# power_supply.net
KiCad netlist of a schematic drawn in Altium Designer
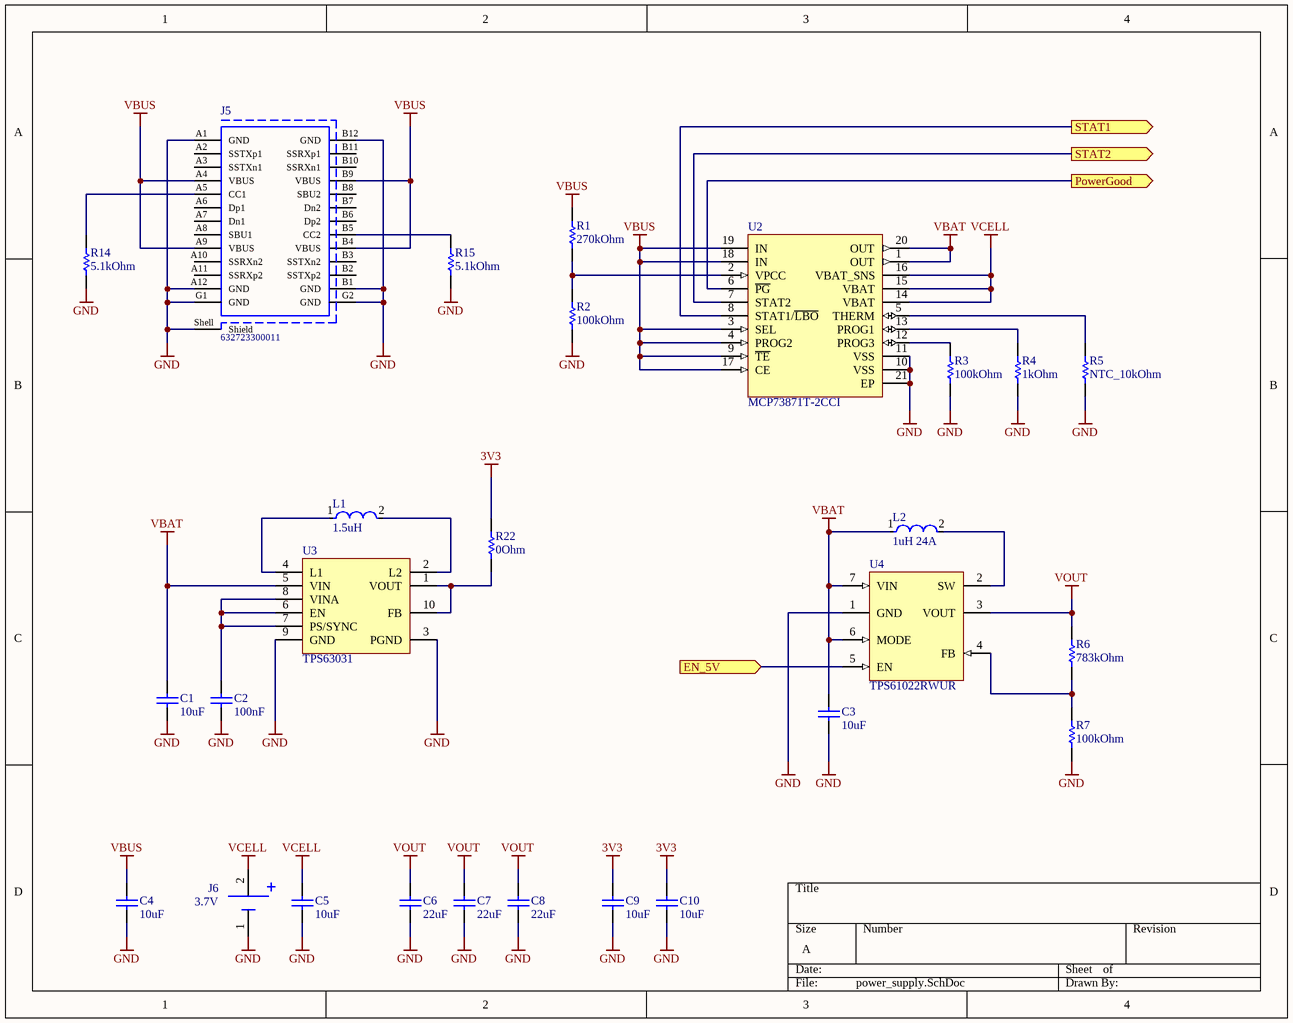
[diagram p0: power_supply.SchDoc]

(export (version "E")
  (design (tool "Eeschema 10.0.6"))
  (components
    (comp (ref "C1")
      (value "10uF")
      (footprint "CAP_0804")
      (fields
        (field (name "TOLERANCE") "10%")
        (field (name "PARTNUMBER") "1206GC102KAT1A")
        (field (name "MANUFACTURER") "AVX")
      )
      (libsource (lib "Schlib") (part "CAP_10UF"))
    )
    (comp (ref "C2")
      (value "100nF")
      (footprint "CAP_0804")
      (fields
        (field (name "TOLERANCE") "10%")
        (field (name "PARTNUMBER") "1206GC102KAT1A")
        (field (name "MANUFACTURER") "AVX")
      )
      (libsource (lib "Schlib") (part "CAP_100NF"))
    )
    (comp (ref "C3")
      (value "10uF")
      (footprint "CAP_0804")
      (fields
        (field (name "TOLERANCE") "10%")
        (field (name "PARTNUMBER") "1206GC102KAT1A")
        (field (name "MANUFACTURER") "AVX")
      )
      (libsource (lib "Schlib") (part "CAP_10UF"))
    )
    (comp (ref "C4")
      (value "10uF")
      (footprint "CAP_0804")
      (fields
        (field (name "TOLERANCE") "10%")
        (field (name "PARTNUMBER") "1206GC102KAT1A")
        (field (name "MANUFACTURER") "AVX")
      )
      (libsource (lib "Schlib") (part "CAP_10UF"))
    )
    (comp (ref "C5")
      (value "10uF")
      (footprint "CAP_0804")
      (fields
        (field (name "TOLERANCE") "10%")
        (field (name "PARTNUMBER") "1206GC102KAT1A")
        (field (name "MANUFACTURER") "AVX")
      )
      (libsource (lib "Schlib") (part "CAP_10UF"))
    )
    (comp (ref "C6")
      (value "22uF")
      (footprint "CAP_0804")
      (fields
        (field (name "TOLERANCE") "10%")
        (field (name "PARTNUMBER") "1206GC102KAT1A")
        (field (name "MANUFACTURER") "AVX")
      )
      (libsource (lib "Schlib") (part "CAP_22UF"))
    )
    (comp (ref "C7")
      (value "22uF")
      (footprint "CAP_0804")
      (fields
        (field (name "TOLERANCE") "10%")
        (field (name "PARTNUMBER") "1206GC102KAT1A")
        (field (name "MANUFACTURER") "AVX")
      )
      (libsource (lib "Schlib") (part "CAP_22UF"))
    )
    (comp (ref "C8")
      (value "22uF")
      (footprint "CAP_0804")
      (fields
        (field (name "TOLERANCE") "10%")
        (field (name "PARTNUMBER") "1206GC102KAT1A")
        (field (name "MANUFACTURER") "AVX")
      )
      (libsource (lib "Schlib") (part "CAP_22UF"))
    )
    (comp (ref "C9")
      (value "10uF")
      (footprint "CAP_0804")
      (fields
        (field (name "TOLERANCE") "10%")
        (field (name "PARTNUMBER") "1206GC102KAT1A")
        (field (name "MANUFACTURER") "AVX")
      )
      (libsource (lib "Schlib") (part "CAP_10UF"))
    )
    (comp (ref "C10")
      (value "10uF")
      (footprint "CAP_0804")
      (fields
        (field (name "TOLERANCE") "10%")
        (field (name "PARTNUMBER") "1206GC102KAT1A")
        (field (name "MANUFACTURER") "AVX")
      )
      (libsource (lib "Schlib") (part "CAP_10UF"))
    )
    (comp (ref "J5")
      (value "632723300011")
      (footprint "USB_C_FEMALE")
      (description "USB 3.1 Type C Receptacle WR-COM, Horizontal, SMT / THT")
      (fields (field (name "MANUFACTURER") "Wurth Elektronik") (field (name "PUBLISHER") "WurthElektronik"))
      (libsource (lib "Schlib") (part "USB_C_FEMALE"))
    )
    (comp (ref "J6")
      (value "3.7V")
      (footprint "BATTERY - duplicate")
      (description "CONN HEADER VERT 2POS 1.25MM")
      (fields
        (field (name "MANUFACTURER PART NUMBER") "53047-0210")
        (field (name "OCTOPART") "https://octopart.com/53047-0210-molex-276772")
      )
      (libsource (lib "Schlib") (part "BATTERY"))
    )
    (comp (ref "L1")
      (value "1.5uH")
      (footprint "INDUCTOR_1.5UH")
      (description "FIXED IND 1.5UH 7A 4.3 MOHM SMD")
      (fields (field (name "MANUFACTURER") "bourns") (field (name "MANUFACTURER PART NUMBER") "SRU1048-1R5Y"))
      (libsource (lib "Schlib") (part "INDUCTOR_1.5UH"))
    )
    (comp (ref "L2")
      (value "1uH 24A")
      (footprint "INDUCTOR_1UH")
      (description "FIXED IND 1UH 24A 3.5 MOHM SMD")
      (fields
        (field (name "OCTOPART") "https://octopart.com/srp1238a-1r0m-bourns-47099079")
        (field (name "MANUFACTURER PART NUMBER") "SRP1238A-1R0M")
      )
      (libsource (lib "Schlib") (part "INDUCTOR_1UH"))
    )
    (comp (ref "R1")
      (value "270kOhm")
      (footprint "RES_0804")
      (fields (field (name "PART NUMBER") "CRCW120647K0FKEA") (field (name "MANUFACTURER") "Vishay Dale"))
      (libsource (lib "Schlib") (part "RES_270K"))
    )
    (comp (ref "R2")
      (value "100kOhm")
      (footprint "RES_0804")
      (fields (field (name "PART NUMBER") "CRCW120647K0FKEA") (field (name "MANUFACTURER") "Vishay Dale"))
      (libsource (lib "Schlib") (part "RES_100K"))
    )
    (comp (ref "R3")
      (value "100kOhm")
      (footprint "RES_0804")
      (fields (field (name "PART NUMBER") "CRCW120647K0FKEA") (field (name "MANUFACTURER") "Vishay Dale"))
      (libsource (lib "Schlib") (part "RES_100K"))
    )
    (comp (ref "R4")
      (value "1kOhm")
      (footprint "RES_0804")
      (fields (field (name "PART NUMBER") "CRCW120647K0FKEA") (field (name "MANUFACTURER") "Vishay Dale"))
      (libsource (lib "Schlib") (part "RES_1K"))
    )
    (comp (ref "R5")
      (value "NTC_10kOhm")
      (footprint "RES_0804")
      (fields (field (name "MANUFACTURER") "Vishay Dale") (field (name "PART NUMBER") "NTHS1206N02N1002JE"))
      (libsource (lib "Schlib") (part "NTC_10K"))
    )
    (comp (ref "R6")
      (value "783kOhm")
      (footprint "RES_0804")
      (fields (field (name "PART NUMBER") "CRCW120647K0FKEA") (field (name "MANUFACTURER") "Vishay Dale"))
      (libsource (lib "Schlib") (part "RES_783K"))
    )
    (comp (ref "R7")
      (value "100kOhm")
      (footprint "RES_0804")
      (fields (field (name "PART NUMBER") "CRCW120647K0FKEA") (field (name "MANUFACTURER") "Vishay Dale"))
      (libsource (lib "Schlib") (part "RES_100K"))
    )
    (comp (ref "R14")
      (value "5.1kOhm")
      (footprint "RES_0804")
      (fields (field (name "PART NUMBER") "CRCW120647K0FKEA") (field (name "MANUFACTURER") "Vishay Dale"))
      (libsource (lib "Schlib") (part "RES_5.1K"))
    )
    (comp (ref "R15")
      (value "5.1kOhm")
      (footprint "RES_0804")
      (fields (field (name "PART NUMBER") "CRCW120647K0FKEA") (field (name "MANUFACTURER") "Vishay Dale"))
      (libsource (lib "Schlib") (part "RES_5.1K"))
    )
    (comp (ref "R22")
      (value "0Ohm")
      (footprint "RES_0804")
      (fields (field (name "PART NUMBER") "CRCW120647K0FKEA") (field (name "MANUFACTURER") "Vishay Dale"))
      (libsource (lib "Schlib") (part "RES_0R"))
    )
    (comp (ref "U2")
      (value "MCP73871T-2CCI")
      (footprint "MCP73871T-2CCI")
      (libsource (lib "Schlib") (part "MCP73871T-2CCI"))
    )
    (comp (ref "U3")
      (value "TPS63031")
      (footprint "TPS63031")
      (description "3V3 BUCK BOOST TEXAS INSTRUMENTS - TPS63031DSKT - IC, DC DC CONV, 1A, 10SON, FULL REEL")
      (fields
        (field (name "MANUFACTURER") "Texas Instruments")
        (field (name "MANUFACTURER PART NUMBER") "TPS63031DSKT")
      )
      (libsource (lib "Schlib") (part "TPS63031"))
    )
    (comp (ref "U4")
      (value "TPS61022RWUR")
      (footprint "TPS61022")
      (description "5V BOOST")
      (fields
        (field (name "OCTOPART") "https://octopart.com/tps61022rwur-texas+instruments-100045592")
        (field (name "MANUFACTURER") "Texas Instruments")
      )
      (libsource (lib "Schlib") (part "TPS61022"))
    )
  )
  (nets
    (net (code "1") (name "/EN_5V") (class "Default")
      (node (ref "U4") (pin "5") (pinfunction "EN_5") (pintype "input"))
    )
    (net (code "2") (name "/PowerGood") (class "Default")
      (node (ref "U2") (pin "6") (pinfunction "~{PG}_6") (pintype "open_collector"))
    )
    (net (code "3") (name "/STAT1") (class "Default")
      (node (ref "U2") (pin "8") (pinfunction "STAT1/~{LBO}_8") (pintype "open_collector"))
    )
    (net (code "4") (name "/STAT2") (class "Default")
      (node (ref "U2") (pin "7") (pinfunction "STAT2_7") (pintype "open_collector"))
    )
    (net (code "5") (name "3V3") (class "Default")
      (node (ref "C10") (pin "2") (pinfunction "2_2") (pintype "passive"))
      (node (ref "C9") (pin "2") (pinfunction "2_2") (pintype "passive"))
      (node (ref "R22") (pin "2") (pinfunction "2_2") (pintype "passive"))
    )
    (net (code "6") (name "GND") (class "Default")
      (node (ref "C1") (pin "1") (pinfunction "1_1") (pintype "passive"))
      (node (ref "C10") (pin "1") (pinfunction "1_1") (pintype "passive"))
      (node (ref "C2") (pin "1") (pinfunction "1_1") (pintype "passive"))
      (node (ref "C3") (pin "1") (pinfunction "1_1") (pintype "passive"))
      (node (ref "C4") (pin "1") (pinfunction "1_1") (pintype "passive"))
      (node (ref "C5") (pin "1") (pinfunction "1_1") (pintype "passive"))
      (node (ref "C6") (pin "1") (pinfunction "1_1") (pintype "passive"))
      (node (ref "C7") (pin "1") (pinfunction "1_1") (pintype "passive"))
      (node (ref "C8") (pin "1") (pinfunction "1_1") (pintype "passive"))
      (node (ref "C9") (pin "1") (pinfunction "1_1") (pintype "passive"))
      (node (ref "J5") (pin "A1") (pinfunction "GND_A1") (pintype "passive"))
      (node (ref "J5") (pin "A12") (pinfunction "GND_A12") (pintype "passive"))
      (node (ref "J5") (pin "B1") (pinfunction "GND_B1") (pintype "passive"))
      (node (ref "J5") (pin "B12") (pinfunction "GND_B12") (pintype "passive"))
      (node (ref "J5") (pin "G1") (pinfunction "GND_G1") (pintype "passive"))
      (node (ref "J5") (pin "G2") (pinfunction "GND_G2") (pintype "passive"))
      (node (ref "J5") (pin "Shell") (pinfunction "Shield_Shell") (pintype "passive"))
      (node (ref "J6") (pin "1") (pinfunction "1_1") (pintype "passive"))
      (node (ref "R14") (pin "1") (pinfunction "1_1") (pintype "passive"))
      (node (ref "R15") (pin "1") (pinfunction "1_1") (pintype "passive"))
      (node (ref "R2") (pin "1") (pinfunction "1_1") (pintype "passive"))
      (node (ref "R3") (pin "1") (pinfunction "1_1") (pintype "passive"))
      (node (ref "R4") (pin "1") (pinfunction "1_1") (pintype "passive"))
      (node (ref "R5") (pin "1") (pinfunction "1_1") (pintype "passive"))
      (node (ref "R7") (pin "1") (pinfunction "1_1") (pintype "passive"))
      (node (ref "U2") (pin "10") (pinfunction "VSS_10") (pintype "power_in"))
      (node (ref "U2") (pin "11") (pinfunction "VSS_11") (pintype "power_in"))
      (node (ref "U2") (pin "21") (pinfunction "EP_21") (pintype "power_in"))
      (node (ref "U3") (pin "3") (pinfunction "PGND_3") (pintype "passive"))
      (node (ref "U3") (pin "9") (pinfunction "GND_9") (pintype "passive"))
      (node (ref "U4") (pin "1") (pinfunction "GND_1") (pintype "power_in"))
    )
    (net (code "7") (name "Net-(J5-CC1)") (class "Default")
      (node (ref "J5") (pin "A5") (pinfunction "CC1_A5") (pintype "passive"))
      (node (ref "R14") (pin "2") (pinfunction "2_2") (pintype "passive"))
    )
    (net (code "8") (name "Net-(J5-CC2)") (class "Default")
      (node (ref "J5") (pin "B5") (pinfunction "CC2_B5") (pintype "passive"))
      (node (ref "R15") (pin "2") (pinfunction "2_2") (pintype "passive"))
    )
    (net (code "9") (name "Net-(U2-PROG1)") (class "Default")
      (node (ref "R4") (pin "2") (pinfunction "2_2") (pintype "passive"))
      (node (ref "U2") (pin "13") (pinfunction "PROG1_13") (pintype "bidirectional"))
    )
    (net (code "10") (name "Net-(U2-PROG3)") (class "Default")
      (node (ref "R3") (pin "2") (pinfunction "2_2") (pintype "passive"))
      (node (ref "U2") (pin "12") (pinfunction "PROG3_12") (pintype "bidirectional"))
    )
    (net (code "11") (name "Net-(U2-THERM)") (class "Default")
      (node (ref "R5") (pin "2") (pinfunction "2_2") (pintype "passive"))
      (node (ref "U2") (pin "5") (pinfunction "THERM_5") (pintype "bidirectional"))
    )
    (net (code "12") (name "Net-(U2-VPCC)") (class "Default")
      (node (ref "R1") (pin "1") (pinfunction "1_1") (pintype "passive"))
      (node (ref "R2") (pin "2") (pinfunction "2_2") (pintype "passive"))
      (node (ref "U2") (pin "2") (pinfunction "VPCC_2") (pintype "input"))
    )
    (net (code "13") (name "Net-(U3-EN)") (class "Default")
      (node (ref "C2") (pin "2") (pinfunction "2_2") (pintype "passive"))
      (node (ref "U3") (pin "6") (pinfunction "EN_6") (pintype "passive"))
      (node (ref "U3") (pin "7") (pinfunction "PS/SYNC_7") (pintype "passive"))
      (node (ref "U3") (pin "8") (pinfunction "VINA_8") (pintype "passive"))
    )
    (net (code "14") (name "Net-(U3-FB)") (class "Default")
      (node (ref "R22") (pin "1") (pinfunction "1_1") (pintype "passive"))
      (node (ref "U3") (pin "1") (pinfunction "VOUT_1") (pintype "passive"))
      (node (ref "U3") (pin "10") (pinfunction "FB_10") (pintype "passive"))
    )
    (net (code "15") (name "Net-(U3-L1)") (class "Default")
      (node (ref "L1") (pin "1") (pinfunction "1_1") (pintype "passive"))
      (node (ref "U3") (pin "4") (pinfunction "L1_4") (pintype "passive"))
    )
    (net (code "16") (name "Net-(U3-L2)") (class "Default")
      (node (ref "L1") (pin "2") (pinfunction "2_2") (pintype "passive"))
      (node (ref "U3") (pin "2") (pinfunction "L2_2") (pintype "passive"))
    )
    (net (code "17") (name "Net-(U4-FB)") (class "Default")
      (node (ref "R6") (pin "1") (pinfunction "1_1") (pintype "passive"))
      (node (ref "R7") (pin "2") (pinfunction "2_2") (pintype "passive"))
      (node (ref "U4") (pin "4") (pinfunction "FB_4") (pintype "input"))
    )
    (net (code "18") (name "Net-(U4-SW)") (class "Default")
      (node (ref "L2") (pin "2") (pinfunction "2_2") (pintype "passive"))
      (node (ref "U4") (pin "2") (pinfunction "SW_2") (pintype "power_in"))
    )
    (net (code "19") (name "VBAT") (class "Default")
      (node (ref "C1") (pin "2") (pinfunction "2_2") (pintype "passive"))
      (node (ref "C3") (pin "2") (pinfunction "2_2") (pintype "passive"))
      (node (ref "L2") (pin "1") (pinfunction "1_1") (pintype "passive"))
      (node (ref "U2") (pin "1") (pinfunction "OUT_1") (pintype "output"))
      (node (ref "U2") (pin "20") (pinfunction "OUT_20") (pintype "output"))
      (node (ref "U3") (pin "5") (pinfunction "VIN_5") (pintype "passive"))
      (node (ref "U4") (pin "6") (pinfunction "MODE_6") (pintype "input"))
      (node (ref "U4") (pin "7") (pinfunction "VIN_7") (pintype "input"))
    )
    (net (code "20") (name "VBUS") (class "Default")
      (node (ref "C4") (pin "2") (pinfunction "2_2") (pintype "passive"))
      (node (ref "J5") (pin "A4") (pinfunction "VBUS_A4") (pintype "passive"))
      (node (ref "J5") (pin "A9") (pinfunction "VBUS_A9") (pintype "passive"))
      (node (ref "J5") (pin "B4") (pinfunction "VBUS_B4") (pintype "passive"))
      (node (ref "J5") (pin "B9") (pinfunction "VBUS_B9") (pintype "passive"))
      (node (ref "R1") (pin "2") (pinfunction "2_2") (pintype "passive"))
      (node (ref "U2") (pin "17") (pinfunction "CE_17") (pintype "input"))
      (node (ref "U2") (pin "18") (pinfunction "IN_18") (pintype "power_in"))
      (node (ref "U2") (pin "19") (pinfunction "IN_19") (pintype "power_in"))
      (node (ref "U2") (pin "3") (pinfunction "SEL_3") (pintype "input"))
      (node (ref "U2") (pin "4") (pinfunction "PROG2_4") (pintype "input"))
      (node (ref "U2") (pin "9") (pinfunction "~{TE}_9") (pintype "input"))
    )
    (net (code "21") (name "VCELL") (class "Default")
      (node (ref "C5") (pin "2") (pinfunction "2_2") (pintype "passive"))
      (node (ref "J6") (pin "2") (pinfunction "2_2") (pintype "passive"))
      (node (ref "U2") (pin "14") (pinfunction "VBAT_14") (pintype "power_in"))
      (node (ref "U2") (pin "15") (pinfunction "VBAT_15") (pintype "power_in"))
      (node (ref "U2") (pin "16") (pinfunction "VBAT_SNS_16") (pintype "power_in"))
    )
    (net (code "22") (name "VOUT") (class "Default")
      (node (ref "C6") (pin "2") (pinfunction "2_2") (pintype "passive"))
      (node (ref "C7") (pin "2") (pinfunction "2_2") (pintype "passive"))
      (node (ref "C8") (pin "2") (pinfunction "2_2") (pintype "passive"))
      (node (ref "R6") (pin "2") (pinfunction "2_2") (pintype "passive"))
      (node (ref "U4") (pin "3") (pinfunction "VOUT_3") (pintype "power_in"))
    )
    (net (code "23") (name "unconnected-(J5-Dn1-PadA7)") (class "Default")
      (node (ref "J5") (pin "A7") (pinfunction "Dn1_A7") (pintype "passive"))
    )
    (net (code "24") (name "unconnected-(J5-Dn2-PadB7)") (class "Default")
      (node (ref "J5") (pin "B7") (pinfunction "Dn2_B7") (pintype "passive"))
    )
    (net (code "25") (name "unconnected-(J5-Dp1-PadA6)") (class "Default")
      (node (ref "J5") (pin "A6") (pinfunction "Dp1_A6") (pintype "passive"))
    )
    (net (code "26") (name "unconnected-(J5-Dp2-PadB6)") (class "Default")
      (node (ref "J5") (pin "B6") (pinfunction "Dp2_B6") (pintype "passive"))
    )
    (net (code "27") (name "unconnected-(J5-SBU1-PadA8)") (class "Default")
      (node (ref "J5") (pin "A8") (pinfunction "SBU1_A8") (pintype "passive"))
    )
    (net (code "28") (name "unconnected-(J5-SBU2-PadB8)") (class "Default")
      (node (ref "J5") (pin "B8") (pinfunction "SBU2_B8") (pintype "passive"))
    )
    (net (code "29") (name "unconnected-(J5-SSRXn1-PadB10)") (class "Default")
      (node (ref "J5") (pin "B10") (pinfunction "SSRXn1_B10") (pintype "passive"))
    )
    (net (code "30") (name "unconnected-(J5-SSRXn2-PadA10)") (class "Default")
      (node (ref "J5") (pin "A10") (pinfunction "SSRXn2_A10") (pintype "passive"))
    )
    (net (code "31") (name "unconnected-(J5-SSRXp1-PadB11)") (class "Default")
      (node (ref "J5") (pin "B11") (pinfunction "SSRXp1_B11") (pintype "passive"))
    )
    (net (code "32") (name "unconnected-(J5-SSRXp2-PadA11)") (class "Default")
      (node (ref "J5") (pin "A11") (pinfunction "SSRXp2_A11") (pintype "passive"))
    )
    (net (code "33") (name "unconnected-(J5-SSTXn1-PadA3)") (class "Default")
      (node (ref "J5") (pin "A3") (pinfunction "SSTXn1_A3") (pintype "passive"))
    )
    (net (code "34") (name "unconnected-(J5-SSTXn2-PadB3)") (class "Default")
      (node (ref "J5") (pin "B3") (pinfunction "SSTXn2_B3") (pintype "passive"))
    )
    (net (code "35") (name "unconnected-(J5-SSTXp1-PadA2)") (class "Default")
      (node (ref "J5") (pin "A2") (pinfunction "SSTXp1_A2") (pintype "passive"))
    )
    (net (code "36") (name "unconnected-(J5-SSTXp2-PadB2)") (class "Default")
      (node (ref "J5") (pin "B2") (pinfunction "SSTXp2_B2") (pintype "passive"))
    )
  )
)
